# PowerCircuit.net
KiCad netlist of a schematic drawn in Altium Designer
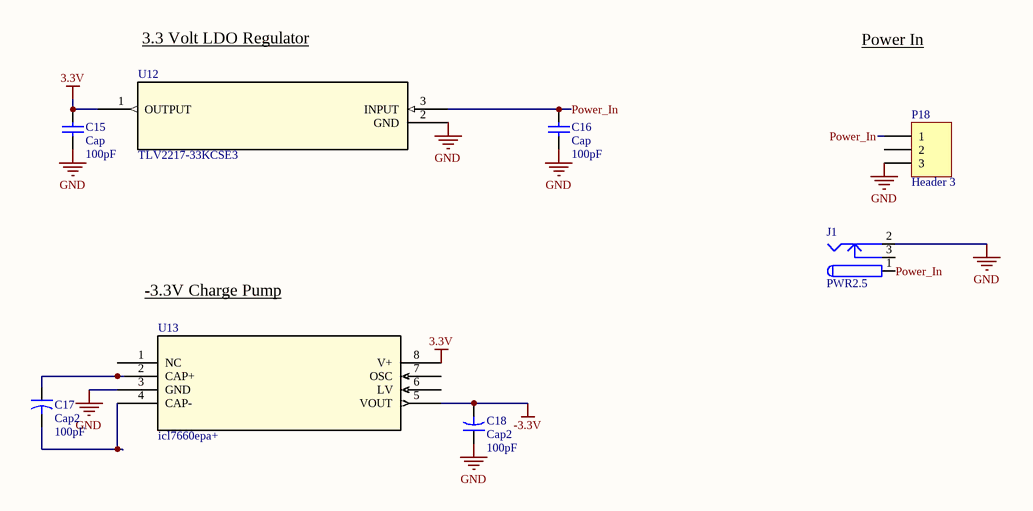
[diagram p0: PowerCircuit.SchDoc]

(export (version "E")
  (design (tool "Eeschema 10.0.6"))
  (components
    (comp (ref "C15")
      (value "Cap")
      (footprint "RAD-0.3")
      (description "Capacitor")
      (fields (field (name "ALTIUM_VALUE") "100pF") (field (name "PUBLISHER") "Altium Limited"))
      (libsource (lib "Miscellaneous Devices") (part "Cap"))
    )
    (comp (ref "C16")
      (value "Cap")
      (footprint "RAD-0.3")
      (description "Capacitor")
      (fields (field (name "ALTIUM_VALUE") "100pF") (field (name "PUBLISHER") "Altium Limited"))
      (libsource (lib "Miscellaneous Devices") (part "Cap"))
    )
    (comp (ref "C17")
      (value "Cap2")
      (footprint "CAPR5-4X5")
      (description "Capacitor")
      (fields (field (name "ALTIUM_VALUE") "100pF") (field (name "PUBLISHER") "Altium Limited"))
      (libsource (lib "Miscellaneous Devices") (part "Cap2"))
    )
    (comp (ref "C18")
      (value "Cap2")
      (footprint "CAPR5-4X5")
      (description "Capacitor")
      (fields (field (name "ALTIUM_VALUE") "100pF") (field (name "PUBLISHER") "Altium Limited"))
      (libsource (lib "Miscellaneous Devices") (part "Cap2"))
    )
    (comp (ref "J1")
      (value "PWR2.5")
      (footprint "Power 2.5 fixed")
      (description "Low Voltage Power Supply Connector")
      (fields (field (name "PUBLISHER") "Altium Limited"))
      (libsource (lib "ECE LIB new") (part "PWR2.5"))
    )
    (comp (ref "P18")
      (value "Header 3")
      (footprint "HDR1X3")
      (description "Header, 3-Pin")
      (fields (field (name "PUBLISHER") "Altium Limited"))
      (libsource (lib "Miscellaneous Connectors") (part "Header 3"))
    )
    (comp (ref "U12")
      (value "TLV2217-33KCSE3")
      (footprint "KCS3")
      (description "Single Output LDO, 500mA, Fixed(1.8V), Output Accuracy of 2%, Thermal Overload Protection")
      (fields
        (field (name "GENERIC_PART_NUMBER") "TLV2217-18")
        (field (name "MANUFACTURER") "Texas Instruments")
        (field (name "COPYRIGHT") "Copyright (C) 2018 Accelerated Designs. All rights reserved")
      )
      (libsource (lib "TLV221733KCSE3") (part "TLV2217-33KCSE3"))
    )
    (comp (ref "U13")
      (value "icl7660epa+")
      (footprint "21-0043D_8_MXM")
      (description "No Description Available")
      (fields (field (name "COPYRIGHT") "Copyright (C) 2018 Accelerated Designs. All rights reserved"))
      (libsource (lib "ICL7660EPA") (part "icl7660epa+"))
    )
  )
  (nets
    (net (code "1") (name "-3.3V") (class "Default")
      (node (ref "C18") (pin "2") (pinfunction "2_2") (pintype "passive"))
      (node (ref "U13") (pin "5") (pinfunction "VOUT_5") (pintype "output"))
    )
    (net (code "2") (name "/Power_In") (class "Default")
      (node (ref "C16") (pin "1") (pinfunction "1_1") (pintype "passive"))
      (node (ref "J1") (pin "1") (pinfunction "1A_1") (pintype "power_in"))
      (node (ref "P18") (pin "1") (pinfunction "1_1") (pintype "passive"))
      (node (ref "U12") (pin "3") (pinfunction "INPUT_3") (pintype "input"))
    )
    (net (code "3") (name "3.3V") (class "Default")
      (node (ref "C15") (pin "1") (pinfunction "1_1") (pintype "passive"))
      (node (ref "U12") (pin "1") (pinfunction "OUTPUT_1") (pintype "output"))
      (node (ref "U13") (pin "8") (pinfunction "V+_8") (pintype "power_in"))
    )
    (net (code "4") (name "GND") (class "Default")
      (node (ref "C15") (pin "2") (pinfunction "2_2") (pintype "passive"))
      (node (ref "C16") (pin "2") (pinfunction "2_2") (pintype "passive"))
      (node (ref "C18") (pin "1") (pinfunction "1_1") (pintype "passive"))
      (node (ref "J1") (pin "2") (pinfunction "2A_2") (pintype "power_in"))
      (node (ref "P18") (pin "3") (pinfunction "3_3") (pintype "passive"))
      (node (ref "U12") (pin "2") (pinfunction "GND_2") (pintype "power_in"))
      (node (ref "U13") (pin "3") (pinfunction "GND_3") (pintype "power_in"))
    )
    (net (code "5") (name "Net-(U13-CAP+)") (class "Default")
      (node (ref "C17") (pin "1") (pinfunction "1_1") (pintype "passive"))
      (node (ref "U13") (pin "2") (pinfunction "CAP+_2") (pintype "passive"))
    )
    (net (code "6") (name "Net-(U13-CAP-)") (class "Default")
      (node (ref "C17") (pin "2") (pinfunction "2_2") (pintype "passive"))
      (node (ref "U13") (pin "4") (pinfunction "CAP-_4") (pintype "passive"))
    )
    (net (code "7") (name "unconnected-(J1-3A-Pad3)") (class "Default")
      (node (ref "J1") (pin "3") (pinfunction "3A_3") (pintype "power_in"))
    )
    (net (code "8") (name "unconnected-(P18-Pad2)") (class "Default")
      (node (ref "P18") (pin "2") (pinfunction "2_2") (pintype "passive"))
    )
    (net (code "9") (name "unconnected-(U13-LV-Pad6)") (class "Default")
      (node (ref "U13") (pin "6") (pinfunction "LV_6") (pintype "input"))
    )
    (net (code "10") (name "unconnected-(U13-NC-Pad1)") (class "Default")
      (node (ref "U13") (pin "1") (pinfunction "NC_1") (pintype "passive"))
    )
    (net (code "11") (name "unconnected-(U13-OSC-Pad7)") (class "Default")
      (node (ref "U13") (pin "7") (pinfunction "OSC_7") (pintype "input"))
    )
  )
)
